# Sensors.net
KiCad netlist of a schematic drawn in Altium Designer
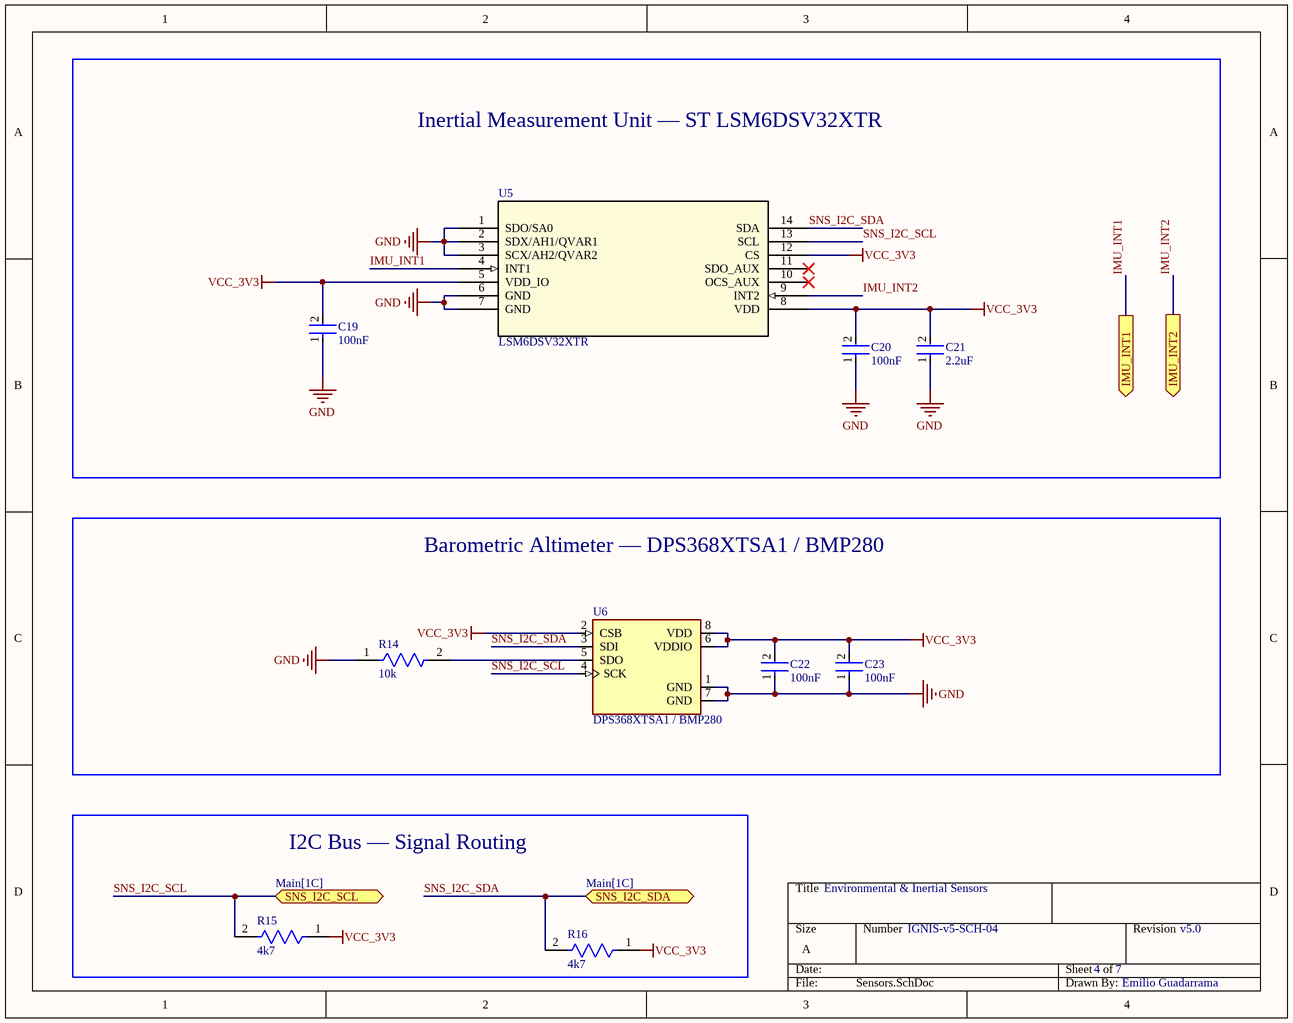
[diagram p0: Sensors.SchDoc]

(export (version "E")
  (design (tool "Eeschema 10.0.6"))
  (components
    (comp (ref "C19")
      (value "100nF")
      (footprint "FP-C0805C-DN-MFG")
      (description "CAP CER 0.1UF 50V X7R 0805")
      (fields
        (field (name "MANUFACTURER PART NUMBER") "C0805C104K5RACTU")
        (field (name "MANUFACTURER") "KEMET")
      )
      (libsource (lib "Altium Content Vault") (part "b4654b650e69147ec39a6b967a45e02"))
    )
    (comp (ref "C20")
      (value "100nF")
      (footprint "FP-C0805C-DN-MFG")
      (description "CAP CER 0.1UF 50V X7R 0805")
      (fields
        (field (name "MANUFACTURER PART NUMBER") "C0805C104K5RACTU")
        (field (name "MANUFACTURER") "KEMET")
      )
      (libsource (lib "Altium Content Vault") (part "b4654b650e69147ec39a6b967a45e02"))
    )
    (comp (ref "C21")
      (value "2.2uF")
      (footprint "FP-C0805C-DN-MFG")
      (description "CAP CER 0.1UF 50V X7R 0805")
      (fields
        (field (name "MANUFACTURER PART NUMBER") "C0805C104K5RACTU")
        (field (name "MANUFACTURER") "KEMET")
      )
      (libsource (lib "Altium Content Vault") (part "b4654b650e69147ec39a6b967a45e02"))
    )
    (comp (ref "C22")
      (value "100nF")
      (footprint "FP-C0805C-DN-MFG")
      (description "CAP CER 0.1UF 50V X7R 0805")
      (fields
        (field (name "MANUFACTURER PART NUMBER") "C0805C104K5RACTU")
        (field (name "MANUFACTURER") "KEMET")
      )
      (libsource (lib "Altium Content Vault") (part "b4654b650e69147ec39a6b967a45e02"))
    )
    (comp (ref "C23")
      (value "100nF")
      (footprint "FP-C0805C-DN-MFG")
      (description "CAP CER 0.1UF 50V X7R 0805")
      (fields
        (field (name "MANUFACTURER PART NUMBER") "C0805C104K5RACTU")
        (field (name "MANUFACTURER") "KEMET")
      )
      (libsource (lib "Altium Content Vault") (part "b4654b650e69147ec39a6b967a45e02"))
    )
    (comp (ref "R14")
      (value "10k")
      (footprint "FP-MCT0603-IPC_A")
      (description "RES SMD 100 OHM 1% 1/8W 0603")
      (fields (field (name "TOLERANCE") "0.1%"))
      (libsource (lib "Altium Content Vault") (part "1029c3af85768c4190bb7ad29bc67b5"))
    )
    (comp (ref "R15")
      (value "4k7")
      (footprint "FP-MCT0603-IPC_A")
      (description "RES SMD 100 OHM 1% 1/8W 0603")
      (fields (field (name "TOLERANCE") "0.1%"))
      (libsource (lib "Altium Content Vault") (part "1029c3af85768c4190bb7ad29bc67b5"))
    )
    (comp (ref "R16")
      (value "4k7")
      (footprint "FP-MCT0603-IPC_A")
      (description "RES SMD 100 OHM 1% 1/8W 0603")
      (fields (field (name "TOLERANCE") "0.1%"))
      (libsource (lib "Altium Content Vault") (part "1029c3af85768c4190bb7ad29bc67b5"))
    )
    (comp (ref "U5")
      (value "LSM6DSV32XTR")
      (footprint "LGA-14L_2p5X3p0X0p86_STM")
      (fields (field (name "COPYRIGHT") "Copyright (C) 2026 Ultra Librarian. All rights reserved."))
      (libsource (lib "LSM6DSV32XTR") (part "LSM6DSV32XTR"))
    )
    (comp (ref "U6")
      (value "DPS368XTSA1 / BMP280")
      (footprint "XDCR_BMP280")
      (description "BMP280 Absolute Barometric Pressure Sensor for Battery Powered Devices 2 x 2.5mm")
      (fields (field (name "MP") "BMP280"))
      (libsource (lib "BMP280") (part "BMP280"))
    )
  )
  (nets
    (net (code "1") (name "/IMU_INT1") (class "Default")
      (node (ref "U5") (pin "4") (pinfunction "INT1_4") (pintype "input"))
    )
    (net (code "2") (name "/IMU_INT2") (class "Default")
      (node (ref "U5") (pin "9") (pinfunction "INT2_9") (pintype "input"))
    )
    (net (code "3") (name "/SNS_I2C_SCL") (class "Default")
      (node (ref "R15") (pin "2") (pinfunction "2_2") (pintype "passive"))
      (node (ref "U5") (pin "13") (pinfunction "SCL_13") (pintype "passive"))
      (node (ref "U6") (pin "4") (pinfunction "SCK_4") (pintype "input"))
    )
    (net (code "4") (name "/SNS_I2C_SDA") (class "Default")
      (node (ref "R16") (pin "2") (pinfunction "2_2") (pintype "passive"))
      (node (ref "U5") (pin "14") (pinfunction "SDA_14") (pintype "passive"))
      (node (ref "U6") (pin "3") (pinfunction "SDI_3") (pintype "bidirectional"))
    )
    (net (code "5") (name "GND") (class "Default")
      (node (ref "C19") (pin "1") (pinfunction "1_1") (pintype "passive"))
      (node (ref "C20") (pin "1") (pinfunction "1_1") (pintype "passive"))
      (node (ref "C21") (pin "1") (pinfunction "1_1") (pintype "passive"))
      (node (ref "C22") (pin "1") (pinfunction "1_1") (pintype "passive"))
      (node (ref "C23") (pin "1") (pinfunction "1_1") (pintype "passive"))
      (node (ref "R14") (pin "1") (pinfunction "1_1") (pintype "passive"))
      (node (ref "U5") (pin "1") (pinfunction "SDO/SA0_1") (pintype "passive"))
      (node (ref "U5") (pin "2") (pinfunction "SDX/AH1/QVAR1_2") (pintype "passive"))
      (node (ref "U5") (pin "3") (pinfunction "SCX/AH2/QVAR2_3") (pintype "passive"))
      (node (ref "U5") (pin "6") (pinfunction "GND_6") (pintype "power_in"))
      (node (ref "U5") (pin "7") (pinfunction "GND_7") (pintype "power_in"))
      (node (ref "U6") (pin "1") (pinfunction "GND_1") (pintype "power_in"))
      (node (ref "U6") (pin "7") (pinfunction "GND_7") (pintype "power_in"))
    )
    (net (code "6") (name "Net-(U6-SDO)") (class "Default")
      (node (ref "R14") (pin "2") (pinfunction "2_2") (pintype "passive"))
      (node (ref "U6") (pin "5") (pinfunction "SDO_5") (pintype "bidirectional"))
    )
    (net (code "7") (name "VCC_3V3") (class "Default")
      (node (ref "C19") (pin "2") (pinfunction "2_2") (pintype "passive"))
      (node (ref "C20") (pin "2") (pinfunction "2_2") (pintype "passive"))
      (node (ref "C21") (pin "2") (pinfunction "2_2") (pintype "passive"))
      (node (ref "C22") (pin "2") (pinfunction "2_2") (pintype "passive"))
      (node (ref "C23") (pin "2") (pinfunction "2_2") (pintype "passive"))
      (node (ref "R15") (pin "1") (pinfunction "1_1") (pintype "passive"))
      (node (ref "R16") (pin "1") (pinfunction "1_1") (pintype "passive"))
      (node (ref "U5") (pin "12") (pinfunction "CS_12") (pintype "passive"))
      (node (ref "U5") (pin "5") (pinfunction "VDD_IO_5") (pintype "power_in"))
      (node (ref "U5") (pin "8") (pinfunction "VDD_8") (pintype "power_in"))
      (node (ref "U6") (pin "2") (pinfunction "CSB_2") (pintype "input"))
      (node (ref "U6") (pin "6") (pinfunction "VDDIO_6") (pintype "power_in"))
      (node (ref "U6") (pin "8") (pinfunction "VDD_8") (pintype "power_in"))
    )
    (net (code "8") (name "unconnected-(U5-OCS_AUX-Pad10)") (class "Default")
      (node (ref "U5") (pin "10") (pinfunction "OCS_AUX_10") (pintype "passive+no_connect"))
    )
    (net (code "9") (name "unconnected-(U5-SDO_AUX-Pad11)") (class "Default")
      (node (ref "U5") (pin "11") (pinfunction "SDO_AUX_11") (pintype "passive+no_connect"))
    )
  )
)
